# SCH2_Main_Computer.net
KiCad netlist of a schematic drawn in Altium Designer
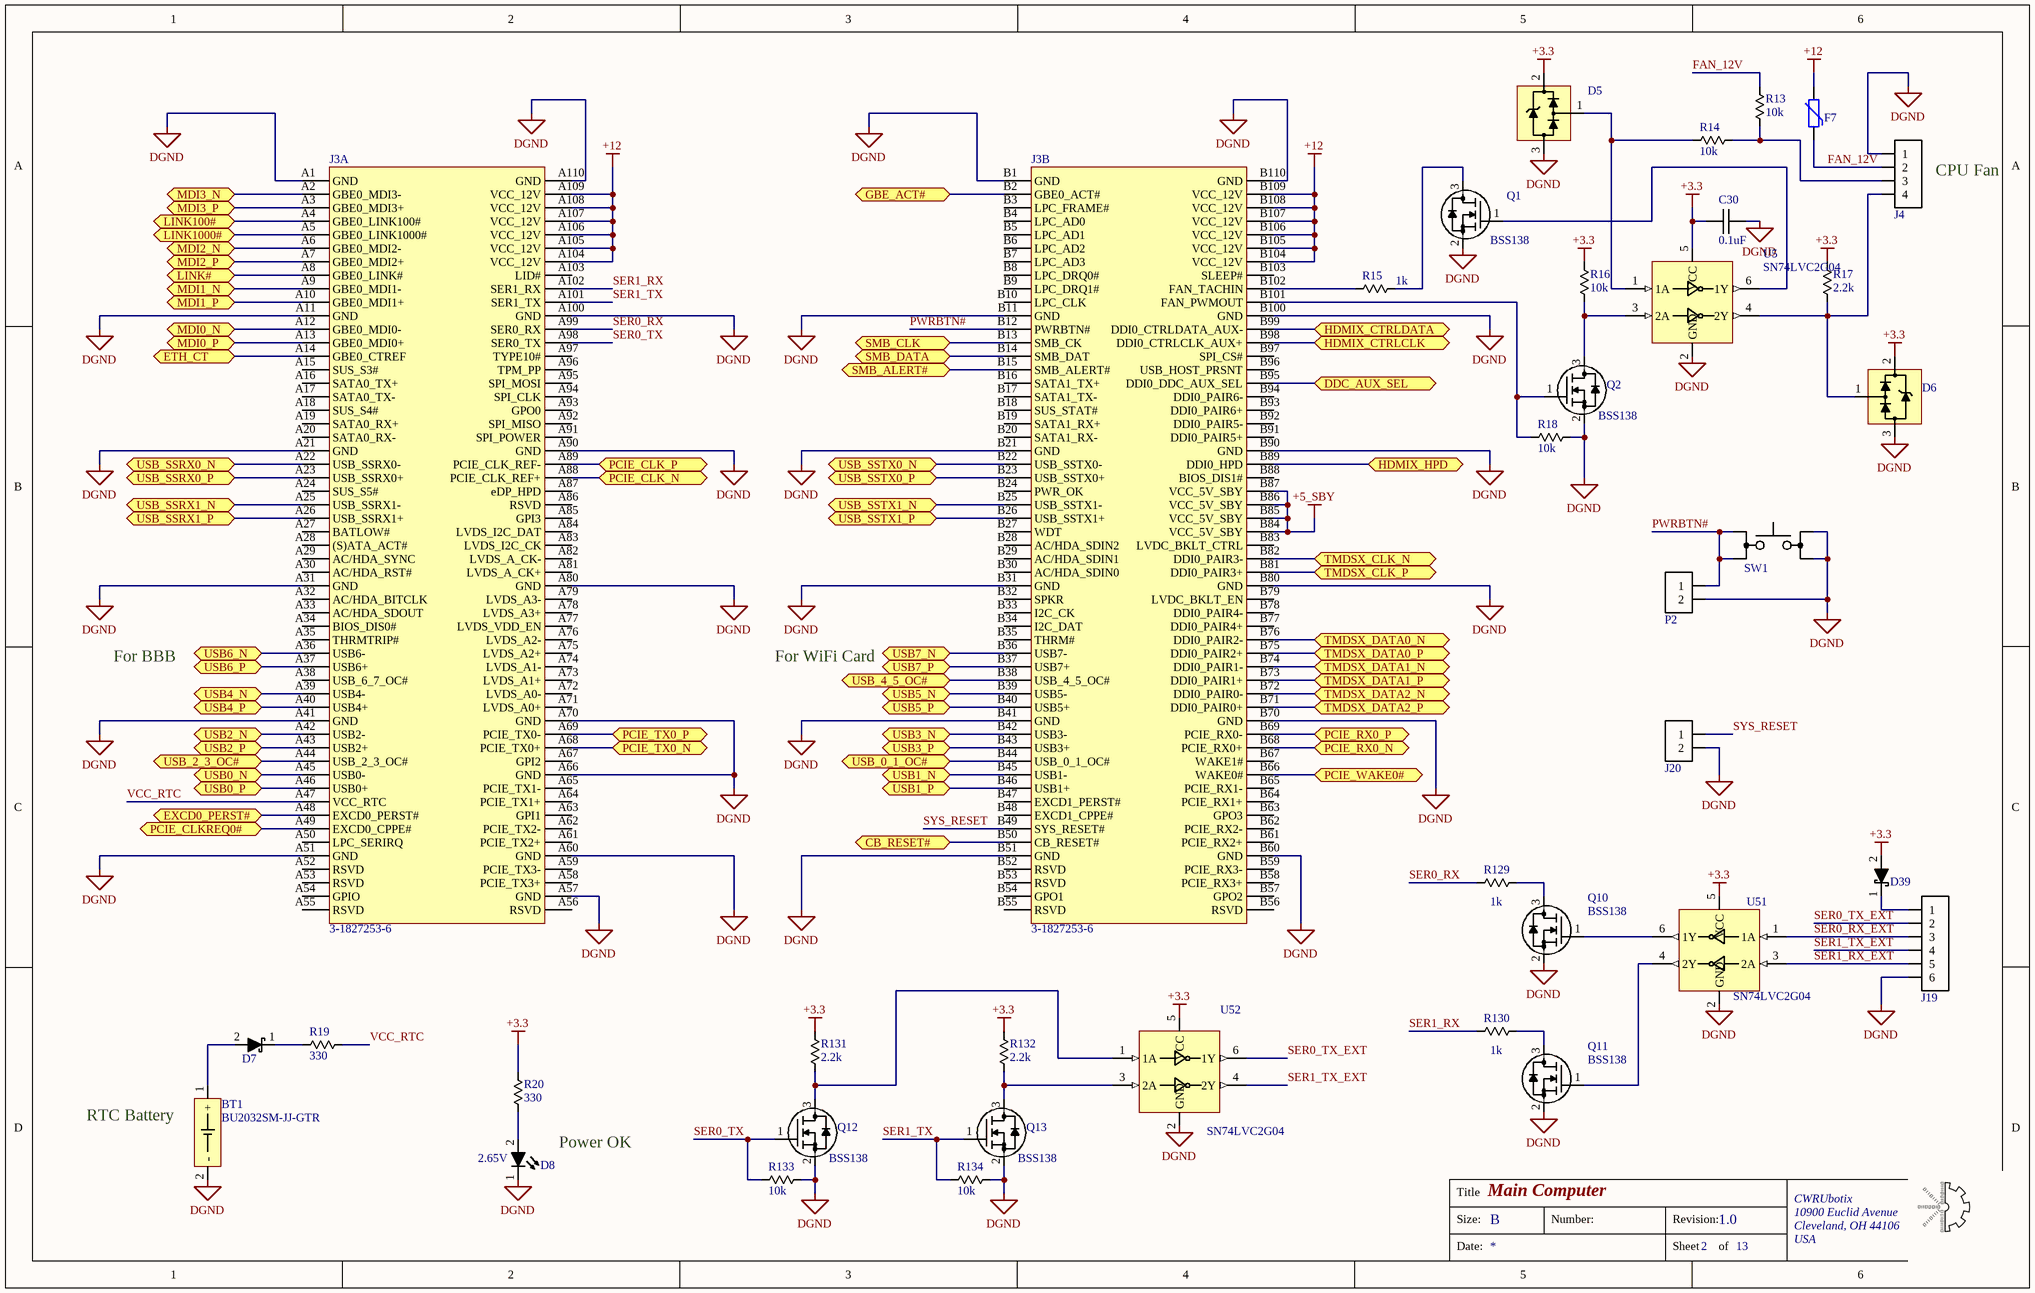
[diagram p0: SCH2_Main_Computer.SchDoc]

(export (version "E")
  (design (tool "Eeschema 10.0.6"))
  (components
    (comp (ref "BT1")
      (value "BU2032SM-JJ-GTR")
      (footprint "BU2032SM-JJ-GTR")
      (description "Battery Holder, Coin Cell CR2032, SMD")
      (fields
        (field (name "PART NUMBER") "CONN-00083")
        (field (name "MANUFACTURER") "Memory Protection Devices")
      )
      (libsource (lib "Connectors$") (part "CONN-00083"))
    )
    (comp (ref "C30")
      (value "0.1uF")
      (footprint "chip_0603")
      (description "CAP, 0.1uF, ±10%, 16V, X7R, 0603")
      (fields (field (name "PART NUMBER") "CAP-00542") (field (name "TOLERANCE") "±10%"))
      (libsource (lib "Capacitors$") (part "CAP-00542"))
    )
    (comp (ref "D5")
      (value "DLPT05")
      (footprint "sot-23-3")
      (description "TVS, Steering (Rail-Rail), 9.8V Clamping, 17A Peak Pulse, SOT-23")
      (fields (field (name "PART NUMBER") "DIO-00057") (field (name "MANUFACTURER") "Diodes Incorporated"))
      (libsource (lib "Diodes$") (part "DIO-00057"))
    )
    (comp (ref "D6")
      (value "DLPT05")
      (footprint "sot-23-3")
      (description "TVS, Steering (Rail-Rail), 9.8V Clamping, 17A Peak Pulse, SOT-23")
      (fields (field (name "PART NUMBER") "DIO-00057") (field (name "MANUFACTURER") "Diodes Incorporated"))
      (libsource (lib "") (part "DIO-00057_1"))
    )
    (comp (ref "D7")
      (value "diode_2")
      (footprint "sod123_0")
      (description "Dio Shtky, 1A, 0.55V, 40V, SOD-123")
      (fields (field (name "PART NUMBER") "DIO-00001") (field (name "MANUFACTURER") "ON Semi"))
      (libsource (lib "Diodes$") (part "DIO-00001"))
    )
    (comp (ref "D8")
      (value "diode_4")
      (footprint "chip_0603_LED")
      (description "LED, Blue, 0603, Low current, HELI2 Series")
      (fields
        (field (name "PART NUMBER") "DIO-00049")
        (field (name "FORWARD VOLTAGE") "2.65V")
        (field (name "MANUFACTURER") "Kingbright")
      )
      (libsource (lib "Diodes$") (part "DIO-00049"))
    )
    (comp (ref "D39")
      (value "diode_2")
      (footprint "sod123_0")
      (description "Dio Shtky, 1A, 0.55V, 40V, SOD-123")
      (fields (field (name "PART NUMBER") "DIO-00001") (field (name "MANUFACTURER") "ON Semi"))
      (libsource (lib "Diodes$") (part "DIO-00001"))
    )
    (comp (ref "F7")
      (value "PTC_0")
      (footprint "chip_1210")
      (description "PTC Fuse (Polyfuse), 16V 1.5A Hold, 3A Trip, 300ms")
      (fields (field (name "PART NUMBER") "MISC-00056") (field (name "MANUFACTURER") "Littelfuse"))
      (libsource (lib "Misc$") (part "MISC-00056"))
    )
    (comp (ref "J3")
      (value "3-1827253-6")
      (footprint "TE_CONN_1827253")
      (description "Plug, 220 pos, COM Express Board-Board connector")
      (fields (field (name "PART NUMBER") "CONN-00078") (field (name "MANUFACTURER") "TE Connectivity"))
      (libsource (lib "Connectors$") (part "CONN-00078"))
    )
    (comp (ref "J4")
      (value "conn-4x1_0")
      (footprint "MOLEX_0470531000")
      (description "Header, 4-Pos, Molex-47053, (CPU Fan Header)")
      (fields (field (name "PART NUMBER") "CONN-00087") (field (name "MANUFACTURER") "Molex"))
      (libsource (lib "Connectors$") (part "CONN-00087"))
    )
    (comp (ref "J19")
      (value "conn-6x1_0")
      (footprint "HDDR_6X1_0")
      (description "Header 6x1, 0.1\"")
      (fields (field (name "PART NUMBER") "CONN-00008"))
      (libsource (lib "Connectors$") (part "CONN-00008"))
    )
    (comp (ref "J20")
      (value "conn-2x1_0")
      (footprint "HDDR_2x1_0")
      (description "Header, 2x1, 0.1\"")
      (fields (field (name "PART NUMBER") "CONN-00055") (field (name "MANUFACTURER") "Samtec"))
      (libsource (lib "Connectors$") (part "CONN-00055"))
    )
    (comp (ref "P2")
      (value "conn-2x1_0")
      (footprint "HDDR_2x1_0")
      (description "Header, 2x1, 0.1\"")
      (fields (field (name "PART NUMBER") "CONN-00055") (field (name "MANUFACTURER") "Samtec"))
      (libsource (lib "Connectors$") (part "CONN-00055"))
    )
    (comp (ref "Q1")
      (value "n-mosfet_1")
      (footprint "sot-23-3")
      (description "XSTR NMOS, 220mA, 50V, Vgs 1.3V, SOT-23-3")
      (fields
        (field (name "PART NUMBER") "XSTR-00017")
        (field (name "MANUFACTURER") "ON Semi")
        (field (name "MANUFACTURER PN") "BSS138")
      )
      (libsource (lib "Transistors$") (part "XSTR-00017"))
    )
    (comp (ref "Q2")
      (value "n-mosfet_1")
      (footprint "sot-23-3")
      (description "XSTR NMOS, 220mA, 50V, Vgs 1.3V, SOT-23-3")
      (fields
        (field (name "PART NUMBER") "XSTR-00017")
        (field (name "MANUFACTURER") "ON Semi")
        (field (name "MANUFACTURER PN") "BSS138")
      )
      (libsource (lib "Transistors$") (part "XSTR-00017"))
    )
    (comp (ref "Q10")
      (value "n-mosfet_1")
      (footprint "sot-23-3")
      (description "XSTR NMOS, 220mA, 50V, Vgs 1.3V, SOT-23-3")
      (fields
        (field (name "PART NUMBER") "XSTR-00017")
        (field (name "MANUFACTURER") "ON Semi")
        (field (name "MANUFACTURER PN") "BSS138")
      )
      (libsource (lib "Transistors$") (part "XSTR-00017"))
    )
    (comp (ref "Q11")
      (value "n-mosfet_1")
      (footprint "sot-23-3")
      (description "XSTR NMOS, 220mA, 50V, Vgs 1.3V, SOT-23-3")
      (fields
        (field (name "PART NUMBER") "XSTR-00017")
        (field (name "MANUFACTURER") "ON Semi")
        (field (name "MANUFACTURER PN") "BSS138")
      )
      (libsource (lib "Transistors$") (part "XSTR-00017"))
    )
    (comp (ref "Q12")
      (value "n-mosfet_1")
      (footprint "sot-23-3")
      (description "XSTR NMOS, 220mA, 50V, Vgs 1.3V, SOT-23-3")
      (fields
        (field (name "PART NUMBER") "XSTR-00017")
        (field (name "MANUFACTURER") "ON Semi")
        (field (name "MANUFACTURER PN") "BSS138")
      )
      (libsource (lib "Transistors$") (part "XSTR-00017"))
    )
    (comp (ref "Q13")
      (value "n-mosfet_1")
      (footprint "sot-23-3")
      (description "XSTR NMOS, 220mA, 50V, Vgs 1.3V, SOT-23-3")
      (fields
        (field (name "PART NUMBER") "XSTR-00017")
        (field (name "MANUFACTURER") "ON Semi")
        (field (name "MANUFACTURER PN") "BSS138")
      )
      (libsource (lib "Transistors$") (part "XSTR-00017"))
    )
    (comp (ref "R13")
      (value "10k")
      (footprint "chip_0603")
      (description "RES SMD 10K OHM 1% 1/4W 0603")
      (fields (field (name "PART NUMBER") "RES-00306") (field (name "TOLERANCE") "1%"))
      (libsource (lib "Resistors$") (part "RES-00306"))
    )
    (comp (ref "R14")
      (value "10k")
      (footprint "chip_0603")
      (description "RES SMD 10K OHM 1% 1/4W 0603")
      (fields (field (name "PART NUMBER") "RES-00306") (field (name "TOLERANCE") "1%"))
      (libsource (lib "Resistors$") (part "RES-00306"))
    )
    (comp (ref "R15")
      (value "1k")
      (footprint "chip_0603")
      (description "RES SMD 1K OHM 1% 1/4W 0603")
      (fields (field (name "PART NUMBER") "RES-00360") (field (name "TOLERANCE") "1%"))
      (libsource (lib "Resistors$") (part "RES-00360"))
    )
    (comp (ref "R16")
      (value "10k")
      (footprint "chip_0603")
      (description "RES SMD 10K OHM 1% 1/4W 0603")
      (fields (field (name "PART NUMBER") "RES-00306") (field (name "TOLERANCE") "1%"))
      (libsource (lib "Resistors$") (part "RES-00306"))
    )
    (comp (ref "R17")
      (value "2.2k")
      (footprint "chip_0603")
      (description "RES SMD 2.2K OHM 1% 1/4W 0603")
      (fields (field (name "PART NUMBER") "RES-00365") (field (name "TOLERANCE") "1%"))
      (libsource (lib "Resistors$") (part "RES-00365"))
    )
    (comp (ref "R18")
      (value "10k")
      (footprint "chip_0603")
      (description "RES SMD 10K OHM 1% 1/4W 0603")
      (fields (field (name "PART NUMBER") "RES-00306") (field (name "TOLERANCE") "1%"))
      (libsource (lib "Resistors$") (part "RES-00306"))
    )
    (comp (ref "R19")
      (value "330")
      (footprint "chip_0603")
      (description "RES SMD 330 OHM 1% 1/4W 0603")
      (fields (field (name "PART NUMBER") "RES-00221") (field (name "TOLERANCE") "1%"))
      (libsource (lib "Resistors$") (part "RES-00221"))
    )
    (comp (ref "R20")
      (value "330")
      (footprint "chip_0603")
      (description "RES SMD 330 OHM 1% 1/4W 0603")
      (fields (field (name "PART NUMBER") "RES-00221") (field (name "TOLERANCE") "1%"))
      (libsource (lib "Resistors$") (part "RES-00221"))
    )
    (comp (ref "R129")
      (value "1k")
      (footprint "chip_0603")
      (description "RES SMD 1K OHM 1% 1/4W 0603")
      (fields (field (name "PART NUMBER") "RES-00360") (field (name "TOLERANCE") "1%"))
      (libsource (lib "Resistors$") (part "RES-00360"))
    )
    (comp (ref "R130")
      (value "1k")
      (footprint "chip_0603")
      (description "RES SMD 1K OHM 1% 1/4W 0603")
      (fields (field (name "PART NUMBER") "RES-00360") (field (name "TOLERANCE") "1%"))
      (libsource (lib "Resistors$") (part "RES-00360"))
    )
    (comp (ref "R131")
      (value "2.2k")
      (footprint "chip_0603")
      (description "RES SMD 2.2K OHM 1% 1/4W 0603")
      (fields (field (name "PART NUMBER") "RES-00365") (field (name "TOLERANCE") "1%"))
      (libsource (lib "Resistors$") (part "RES-00365"))
    )
    (comp (ref "R132")
      (value "2.2k")
      (footprint "chip_0603")
      (description "RES SMD 2.2K OHM 1% 1/4W 0603")
      (fields (field (name "PART NUMBER") "RES-00365") (field (name "TOLERANCE") "1%"))
      (libsource (lib "Resistors$") (part "RES-00365"))
    )
    (comp (ref "R133")
      (value "10k")
      (footprint "chip_0603")
      (description "RES SMD 10K OHM 1% 1/4W 0603")
      (fields (field (name "PART NUMBER") "RES-00306") (field (name "TOLERANCE") "1%"))
      (libsource (lib "Resistors$") (part "RES-00306"))
    )
    (comp (ref "R134")
      (value "10k")
      (footprint "chip_0603")
      (description "RES SMD 10K OHM 1% 1/4W 0603")
      (fields (field (name "PART NUMBER") "RES-00306") (field (name "TOLERANCE") "1%"))
      (libsource (lib "Resistors$") (part "RES-00306"))
    )
    (comp (ref "SW1")
      (value "SW_1P1T_2")
      (footprint "B3FS-1000")
      (description "Switch, SPST-NO, Tactile, 6.3x6.0mm, SMD, 50mA 24VDC")
      (fields (field (name "PART NUMBER") "MISC-00042") (field (name "MANUFACTURER") "Omron"))
      (libsource (lib "Misc$") (part "MISC-00042"))
    )
    (comp (ref "U5")
      (value "SN74LVC2G04")
      (footprint "sot-23-6")
      (description "Inverter, Dual, sot-23-6, SN74LVC2G04")
      (fields (field (name "PART NUMBER") "LOGIC-00001") (field (name "MANUFACTURER") "TI"))
      (libsource (lib "") (part "LOGIC-00001_1"))
    )
    (comp (ref "U51")
      (value "SN74LVC2G04")
      (footprint "sot-23-6")
      (description "Inverter, Dual, sot-23-6, SN74LVC2G04")
      (fields (field (name "PART NUMBER") "LOGIC-00001") (field (name "MANUFACTURER") "TI"))
      (libsource (lib "Logic$") (part "LOGIC-00001"))
    )
    (comp (ref "U52")
      (value "SN74LVC2G04")
      (footprint "sot-23-6")
      (description "Inverter, Dual, sot-23-6, SN74LVC2G04")
      (fields (field (name "PART NUMBER") "LOGIC-00001") (field (name "MANUFACTURER") "TI"))
      (libsource (lib "") (part "LOGIC-00001_1"))
    )
  )
  (nets
    (net (code "1") (name "+3.3") (class "Default")
      (node (ref "C30") (pin "1") (pinfunction "1_1") (pintype "passive"))
      (node (ref "D39") (pin "2") (pinfunction "2_2") (pintype "passive"))
      (node (ref "D5") (pin "2") (pinfunction "VCC_2") (pintype "passive"))
      (node (ref "D6") (pin "2") (pinfunction "VCC_2") (pintype "passive"))
      (node (ref "R131") (pin "1") (pinfunction "1_1") (pintype "passive"))
      (node (ref "R132") (pin "1") (pinfunction "1_1") (pintype "passive"))
      (node (ref "R16") (pin "1") (pinfunction "1_1") (pintype "passive"))
      (node (ref "R17") (pin "1") (pinfunction "1_1") (pintype "passive"))
      (node (ref "R20") (pin "2") (pinfunction "2_2") (pintype "passive"))
      (node (ref "U5") (pin "5") (pinfunction "VCC_5") (pintype "power_in"))
      (node (ref "U51") (pin "5") (pinfunction "VCC_5") (pintype "power_in"))
      (node (ref "U52") (pin "5") (pinfunction "VCC_5") (pintype "power_in"))
    )
    (net (code "2") (name "+5_SBY") (class "Default")
      (node (ref "J3") (pin "B84") (pinfunction "VCC_5V_SBY_B84") (pintype "passive"))
      (node (ref "J3") (pin "B85") (pinfunction "VCC_5V_SBY_B85") (pintype "passive"))
      (node (ref "J3") (pin "B86") (pinfunction "VCC_5V_SBY_B86") (pintype "passive"))
      (node (ref "J3") (pin "B87") (pinfunction "VCC_5V_SBY_B87") (pintype "passive"))
    )
    (net (code "3") (name "+12") (class "Default")
      (node (ref "F7") (pin "2") (pinfunction "2_2") (pintype "passive"))
      (node (ref "J3") (pin "A104") (pinfunction "VCC_12V_A104") (pintype "passive"))
      (node (ref "J3") (pin "A105") (pinfunction "VCC_12V_A105") (pintype "passive"))
      (node (ref "J3") (pin "A106") (pinfunction "VCC_12V_A106") (pintype "passive"))
      (node (ref "J3") (pin "A107") (pinfunction "VCC_12V_A107") (pintype "passive"))
      (node (ref "J3") (pin "A108") (pinfunction "VCC_12V_A108") (pintype "passive"))
      (node (ref "J3") (pin "A109") (pinfunction "VCC_12V_A109") (pintype "passive"))
      (node (ref "J3") (pin "B104") (pinfunction "VCC_12V_B104") (pintype "passive"))
      (node (ref "J3") (pin "B105") (pinfunction "VCC_12V_B105") (pintype "passive"))
      (node (ref "J3") (pin "B106") (pinfunction "VCC_12V_B106") (pintype "passive"))
      (node (ref "J3") (pin "B107") (pinfunction "VCC_12V_B107") (pintype "passive"))
      (node (ref "J3") (pin "B108") (pinfunction "VCC_12V_B108") (pintype "passive"))
      (node (ref "J3") (pin "B109") (pinfunction "VCC_12V_B109") (pintype "passive"))
    )
    (net (code "4") (name "/CB_RESET#") (class "Default")
      (node (ref "J3") (pin "B50") (pinfunction "CB_RESET#_B50") (pintype "passive"))
    )
    (net (code "5") (name "/DDC_AUX_SEL") (class "Default")
      (node (ref "J3") (pin "B95") (pinfunction "DDI0_DDC_AUX_SEL_B95") (pintype "passive"))
    )
    (net (code "6") (name "/ETH_CT") (class "Default")
      (node (ref "J3") (pin "A14") (pinfunction "GBE0_CTREF_A14") (pintype "passive"))
    )
    (net (code "7") (name "/EXCD0_PERST#") (class "Default")
      (node (ref "J3") (pin "A48") (pinfunction "EXCD0_PERST#_A48") (pintype "passive"))
    )
    (net (code "8") (name "/FAN_12V") (class "Default")
      (node (ref "F7") (pin "1") (pinfunction "1_1") (pintype "passive"))
      (node (ref "J4") (pin "2") (pinfunction "2_2") (pintype "passive"))
      (node (ref "R13") (pin "2") (pinfunction "2_2") (pintype "passive"))
    )
    (net (code "9") (name "/GBE_ACT#") (class "Default")
      (node (ref "J3") (pin "B2") (pinfunction "GBE0_ACT#_B2") (pintype "passive"))
    )
    (net (code "10") (name "/HDMIX_CTRLCLK") (class "Default")
      (node (ref "J3") (pin "B98") (pinfunction "DDI0_CTRLCLK_AUX+_B98") (pintype "passive"))
    )
    (net (code "11") (name "/HDMIX_CTRLDATA") (class "Default")
      (node (ref "J3") (pin "B99") (pinfunction "DDI0_CTRLDATA_AUX-_B99") (pintype "passive"))
    )
    (net (code "12") (name "/HDMIX_HPD") (class "Default")
      (node (ref "J3") (pin "B89") (pinfunction "DDI0_HPD_B89") (pintype "passive"))
    )
    (net (code "13") (name "/LINK#") (class "Default")
      (node (ref "J3") (pin "A8") (pinfunction "GBE0_LINK#_A8") (pintype "passive"))
    )
    (net (code "14") (name "/LINK100#") (class "Default")
      (node (ref "J3") (pin "A4") (pinfunction "GBE0_LINK100#_A4") (pintype "passive"))
    )
    (net (code "15") (name "/LINK1000#") (class "Default")
      (node (ref "J3") (pin "A5") (pinfunction "GBE0_LINK1000#_A5") (pintype "passive"))
    )
    (net (code "16") (name "/MDI0_N") (class "Default")
      (node (ref "J3") (pin "A12") (pinfunction "GBE0_MDI0-_A12") (pintype "passive"))
    )
    (net (code "17") (name "/MDI0_P") (class "Default")
      (node (ref "J3") (pin "A13") (pinfunction "GBE0_MDI0+_A13") (pintype "passive"))
    )
    (net (code "18") (name "/MDI1_N") (class "Default")
      (node (ref "J3") (pin "A9") (pinfunction "GBE0_MDI1-_A9") (pintype "passive"))
    )
    (net (code "19") (name "/MDI1_P") (class "Default")
      (node (ref "J3") (pin "A10") (pinfunction "GBE0_MDI1+_A10") (pintype "passive"))
    )
    (net (code "20") (name "/MDI2_N") (class "Default")
      (node (ref "J3") (pin "A6") (pinfunction "GBE0_MDI2-_A6") (pintype "passive"))
    )
    (net (code "21") (name "/MDI2_P") (class "Default")
      (node (ref "J3") (pin "A7") (pinfunction "GBE0_MDI2+_A7") (pintype "passive"))
    )
    (net (code "22") (name "/MDI3_N") (class "Default")
      (node (ref "J3") (pin "A2") (pinfunction "GBE0_MDI3-_A2") (pintype "passive"))
    )
    (net (code "23") (name "/MDI3_P") (class "Default")
      (node (ref "J3") (pin "A3") (pinfunction "GBE0_MDI3+_A3") (pintype "passive"))
    )
    (net (code "24") (name "/PCIE_CLKREQ0#") (class "Default")
      (node (ref "J3") (pin "A49") (pinfunction "EXCD0_CPPE#_A49") (pintype "passive"))
    )
    (net (code "25") (name "/PCIE_CLK_N") (class "Default")
      (node (ref "J3") (pin "A88") (pinfunction "PCIE_CLK_REF+_A88") (pintype "passive"))
    )
    (net (code "26") (name "/PCIE_CLK_P") (class "Default")
      (node (ref "J3") (pin "A89") (pinfunction "PCIE_CLK_REF-_A89") (pintype "passive"))
    )
    (net (code "27") (name "/PCIE_RX0_N") (class "Default")
      (node (ref "J3") (pin "B68") (pinfunction "PCIE_RX0+_B68") (pintype "passive"))
    )
    (net (code "28") (name "/PCIE_RX0_P") (class "Default")
      (node (ref "J3") (pin "B69") (pinfunction "PCIE_RX0-_B69") (pintype "passive"))
    )
    (net (code "29") (name "/PCIE_TX0_N") (class "Default")
      (node (ref "J3") (pin "A68") (pinfunction "PCIE_TX0+_A68") (pintype "passive"))
    )
    (net (code "30") (name "/PCIE_TX0_P") (class "Default")
      (node (ref "J3") (pin "A69") (pinfunction "PCIE_TX0-_A69") (pintype "passive"))
    )
    (net (code "31") (name "/PCIE_WAKE0#") (class "Default")
      (node (ref "J3") (pin "B66") (pinfunction "WAKE0#_B66") (pintype "passive"))
    )
    (net (code "32") (name "/PWRBTN#") (class "Default")
      (node (ref "J3") (pin "B12") (pinfunction "PWRBTN#_B12") (pintype "passive"))
      (node (ref "P2") (pin "1") (pinfunction "1_1") (pintype "passive"))
      (node (ref "SW1") (pin "1") (pinfunction "1_1") (pintype "passive"))
      (node (ref "SW1") (pin "2") (pinfunction "2_2") (pintype "passive"))
    )
    (net (code "33") (name "/SER0_RX") (class "Default")
      (node (ref "J3") (pin "A99") (pinfunction "SER0_RX_A99") (pintype "passive"))
      (node (ref "R129") (pin "1") (pinfunction "1_1") (pintype "passive"))
    )
    (net (code "34") (name "/SER0_RX_EXT") (class "Default")
      (node (ref "J19") (pin "3") (pinfunction "3_3") (pintype "passive"))
      (node (ref "U51") (pin "1") (pinfunction "1A_1") (pintype "input"))
    )
    (net (code "35") (name "/SER0_TX") (class "Default")
      (node (ref "J3") (pin "A98") (pinfunction "SER0_TX_A98") (pintype "passive"))
      (node (ref "Q12") (pin "1") (pinfunction "G_1") (pintype "passive"))
      (node (ref "R133") (pin "1") (pinfunction "1_1") (pintype "passive"))
    )
    (net (code "36") (name "/SER0_TX_EXT") (class "Default")
      (node (ref "J19") (pin "2") (pinfunction "2_2") (pintype "passive"))
      (node (ref "U52") (pin "6") (pinfunction "1Y_6") (pintype "output"))
    )
    (net (code "37") (name "/SER1_RX") (class "Default")
      (node (ref "J3") (pin "A102") (pinfunction "SER1_RX_A102") (pintype "passive"))
      (node (ref "R130") (pin "1") (pinfunction "1_1") (pintype "passive"))
    )
    (net (code "38") (name "/SER1_RX_EXT") (class "Default")
      (node (ref "J19") (pin "5") (pinfunction "5_5") (pintype "passive"))
      (node (ref "U51") (pin "3") (pinfunction "2A_3") (pintype "input"))
    )
    (net (code "39") (name "/SER1_TX") (class "Default")
      (node (ref "J3") (pin "A101") (pinfunction "SER1_TX_A101") (pintype "passive"))
      (node (ref "Q13") (pin "1") (pinfunction "G_1") (pintype "passive"))
      (node (ref "R134") (pin "1") (pinfunction "1_1") (pintype "passive"))
    )
    (net (code "40") (name "/SER1_TX_EXT") (class "Default")
      (node (ref "J19") (pin "4") (pinfunction "4_4") (pintype "passive"))
      (node (ref "U52") (pin "4") (pinfunction "2Y_4") (pintype "output"))
    )
    (net (code "41") (name "/SMB_ALERT#") (class "Default")
      (node (ref "J3") (pin "B15") (pinfunction "SMB_ALERT#_B15") (pintype "passive"))
    )
    (net (code "42") (name "/SMB_CLK") (class "Default")
      (node (ref "J3") (pin "B13") (pinfunction "SMB_CK_B13") (pintype "passive"))
    )
    (net (code "43") (name "/SMB_DATA") (class "Default")
      (node (ref "J3") (pin "B14") (pinfunction "SMB_DAT_B14") (pintype "passive"))
    )
    (net (code "44") (name "/SYS_RESET") (class "Default")
      (node (ref "J20") (pin "1") (pinfunction "1_1") (pintype "passive"))
      (node (ref "J3") (pin "B49") (pinfunction "SYS_RESET#_B49") (pintype "passive"))
    )
    (net (code "45") (name "/TMDSX_CLK_N") (class "Default")
      (node (ref "J3") (pin "B82") (pinfunction "DDI0_PAIR3-_B82") (pintype "passive"))
    )
    (net (code "46") (name "/TMDSX_CLK_P") (class "Default")
      (node (ref "J3") (pin "B81") (pinfunction "DDI0_PAIR3+_B81") (pintype "passive"))
    )
    (net (code "47") (name "/TMDSX_DATA0_N") (class "Default")
      (node (ref "J3") (pin "B76") (pinfunction "DDI0_PAIR2-_B76") (pintype "passive"))
    )
    (net (code "48") (name "/TMDSX_DATA0_P") (class "Default")
      (node (ref "J3") (pin "B75") (pinfunction "DDI0_PAIR2+_B75") (pintype "passive"))
    )
    (net (code "49") (name "/TMDSX_DATA1_N") (class "Default")
      (node (ref "J3") (pin "B74") (pinfunction "DDI0_PAIR1-_B74") (pintype "passive"))
    )
    (net (code "50") (name "/TMDSX_DATA1_P") (class "Default")
      (node (ref "J3") (pin "B73") (pinfunction "DDI0_PAIR1+_B73") (pintype "passive"))
    )
    (net (code "51") (name "/TMDSX_DATA2_N") (class "Default")
      (node (ref "J3") (pin "B72") (pinfunction "DDI0_PAIR0-_B72") (pintype "passive"))
    )
    (net (code "52") (name "/TMDSX_DATA2_P") (class "Default")
      (node (ref "J3") (pin "B71") (pinfunction "DDI0_PAIR0+_B71") (pintype "passive"))
    )
    (net (code "53") (name "/USB0_N") (class "Default")
      (node (ref "J3") (pin "A45") (pinfunction "USB0-_A45") (pintype "passive"))
    )
    (net (code "54") (name "/USB0_P") (class "Default")
      (node (ref "J3") (pin "A46") (pinfunction "USB0+_A46") (pintype "passive"))
    )
    (net (code "55") (name "/USB1_N") (class "Default")
      (node (ref "J3") (pin "B45") (pinfunction "USB1-_B45") (pintype "passive"))
    )
    (net (code "56") (name "/USB1_P") (class "Default")
      (node (ref "J3") (pin "B46") (pinfunction "USB1+_B46") (pintype "passive"))
    )
    (net (code "57") (name "/USB2_N") (class "Default")
      (node (ref "J3") (pin "A42") (pinfunction "USB2-_A42") (pintype "passive"))
    )
    (net (code "58") (name "/USB2_P") (class "Default")
      (node (ref "J3") (pin "A43") (pinfunction "USB2+_A43") (pintype "passive"))
    )
    (net (code "59") (name "/USB3_N") (class "Default")
      (node (ref "J3") (pin "B42") (pinfunction "USB3-_B42") (pintype "passive"))
    )
    (net (code "60") (name "/USB3_P") (class "Default")
      (node (ref "J3") (pin "B43") (pinfunction "USB3+_B43") (pintype "passive"))
    )
    (net (code "61") (name "/USB4_N") (class "Default")
      (node (ref "J3") (pin "A39") (pinfunction "USB4-_A39") (pintype "passive"))
    )
    (net (code "62") (name "/USB4_P") (class "Default")
      (node (ref "J3") (pin "A40") (pinfunction "USB4+_A40") (pintype "passive"))
    )
    (net (code "63") (name "/USB5_N") (class "Default")
      (node (ref "J3") (pin "B39") (pinfunction "USB5-_B39") (pintype "passive"))
    )
    (net (code "64") (name "/USB5_P") (class "Default")
      (node (ref "J3") (pin "B40") (pinfunction "USB5+_B40") (pintype "passive"))
    )
    (net (code "65") (name "/USB6_N") (class "Default")
      (node (ref "J3") (pin "A36") (pinfunction "USB6-_A36") (pintype "passive"))
    )
    (net (code "66") (name "/USB6_P") (class "Default")
      (node (ref "J3") (pin "A37") (pinfunction "USB6+_A37") (pintype "passive"))
    )
    (net (code "67") (name "/USB7_N") (class "Default")
      (node (ref "J3") (pin "B36") (pinfunction "USB7-_B36") (pintype "passive"))
    )
    (net (code "68") (name "/USB7_P") (class "Default")
      (node (ref "J3") (pin "B37") (pinfunction "USB7+_B37") (pintype "passive"))
    )
    (net (code "69") (name "/USB_0_1_OC#") (class "Default")
      (node (ref "J3") (pin "B44") (pinfunction "USB_0_1_OC#_B44") (pintype "passive"))
    )
    (net (code "70") (name "/USB_2_3_OC#") (class "Default")
      (node (ref "J3") (pin "A44") (pinfunction "USB_2_3_OC#_A44") (pintype "passive"))
    )
    (net (code "71") (name "/USB_4_5_OC#") (class "Default")
      (node (ref "J3") (pin "B38") (pinfunction "USB_4_5_OC#_B38") (pintype "passive"))
    )
    (net (code "72") (name "/USB_SSRX0_N") (class "Default")
      (node (ref "J3") (pin "A22") (pinfunction "USB_SSRX0-_A22") (pintype "passive"))
    )
    (net (code "73") (name "/USB_SSRX0_P") (class "Default")
      (node (ref "J3") (pin "A23") (pinfunction "USB_SSRX0+_A23") (pintype "passive"))
    )
    (net (code "74") (name "/USB_SSRX1_N") (class "Default")
      (node (ref "J3") (pin "A25") (pinfunction "USB_SSRX1-_A25") (pintype "passive"))
    )
    (net (code "75") (name "/USB_SSRX1_P") (class "Default")
      (node (ref "J3") (pin "A26") (pinfunction "USB_SSRX1+_A26") (pintype "passive"))
    )
    (net (code "76") (name "/USB_SSTX0_N") (class "Default")
      (node (ref "J3") (pin "B22") (pinfunction "USB_SSTX0-_B22") (pintype "passive"))
    )
    (net (code "77") (name "/USB_SSTX0_P") (class "Default")
      (node (ref "J3") (pin "B23") (pinfunction "USB_SSTX0+_B23") (pintype "passive"))
    )
    (net (code "78") (name "/USB_SSTX1_N") (class "Default")
      (node (ref "J3") (pin "B25") (pinfunction "USB_SSTX1-_B25") (pintype "passive"))
    )
    (net (code "79") (name "/USB_SSTX1_P") (class "Default")
      (node (ref "J3") (pin "B26") (pinfunction "USB_SSTX1+_B26") (pintype "passive"))
    )
    (net (code "80") (name "/VCC_RTC") (class "Default")
      (node (ref "J3") (pin "A47") (pinfunction "VCC_RTC_A47") (pintype "passive"))
      (node (ref "R19") (pin "2") (pinfunction "2_2") (pintype "passive"))
    )
    (net (code "81") (name "DGND") (class "Default")
      (node (ref "BT1") (pin "2") (pinfunction "-_2") (pintype "passive"))
      (node (ref "C30") (pin "2") (pinfunction "2_2") (pintype "passive"))
      (node (ref "D5") (pin "3") (pinfunction "GND_3") (pintype "passive"))
      (node (ref "D6") (pin "3") (pinfunction "GND_3") (pintype "passive"))
      (node (ref "D8") (pin "1") (pinfunction "1_1") (pintype "passive"))
      (node (ref "J19") (pin "6") (pinfunction "6_6") (pintype "passive"))
      (node (ref "J20") (pin "2") (pinfunction "2_2") (pintype "passive"))
      (node (ref "J3") (pin "A1") (pinfunction "GND_A1") (pintype "passive"))
      (node (ref "J3") (pin "A100") (pinfunction "GND_A100") (pintype "passive"))
      (node (ref "J3") (pin "A11") (pinfunction "GND_A11") (pintype "passive"))
      (node (ref "J3") (pin "A110") (pinfunction "GND_A110") (pintype "passive"))
      (node (ref "J3") (pin "A21") (pinfunction "GND_A21") (pintype "passive"))
      (node (ref "J3") (pin "A31") (pinfunction "GND_A31") (pintype "passive"))
      (node (ref "J3") (pin "A41") (pinfunction "GND_A41") (pintype "passive"))
      (node (ref "J3") (pin "A51") (pinfunction "GND_A51") (pintype "passive"))
      (node (ref "J3") (pin "A57") (pinfunction "GND_A57") (pintype "passive"))
      (node (ref "J3") (pin "A60") (pinfunction "GND_A60") (pintype "passive"))
      (node (ref "J3") (pin "A66") (pinfunction "GND_A66") (pintype "passive"))
      (node (ref "J3") (pin "A70") (pinfunction "GND_A70") (pintype "passive"))
      (node (ref "J3") (pin "A80") (pinfunction "GND_A80") (pintype "passive"))
      (node (ref "J3") (pin "A90") (pinfunction "GND_A90") (pintype "passive"))
      (node (ref "J3") (pin "B1") (pinfunction "GND_B1") (pintype "passive"))
      (node (ref "J3") (pin "B100") (pinfunction "GND_B100") (pintype "passive"))
      (node (ref "J3") (pin "B11") (pinfunction "GND_B11") (pintype "passive"))
      (node (ref "J3") (pin "B110") (pinfunction "GND_B110") (pintype "passive"))
      (node (ref "J3") (pin "B21") (pinfunction "GND_B21") (pintype "passive"))
      (node (ref "J3") (pin "B31") (pinfunction "GND_B31") (pintype "passive"))
      (node (ref "J3") (pin "B41") (pinfunction "GND_B41") (pintype "passive"))
      (node (ref "J3") (pin "B51") (pinfunction "GND_B51") (pintype "passive"))
      (node (ref "J3") (pin "B60") (pinfunction "GND_B60") (pintype "passive"))
      (node (ref "J3") (pin "B70") (pinfunction "GND_B70") (pintype "passive"))
      (node (ref "J3") (pin "B80") (pinfunction "GND_B80") (pintype "passive"))
      (node (ref "J3") (pin "B90") (pinfunction "GND_B90") (pintype "passive"))
      (node (ref "J4") (pin "1") (pinfunction "1_1") (pintype "passive"))
      (node (ref "P2") (pin "2") (pinfunction "2_2") (pintype "passive"))
      (node (ref "Q1") (pin "2") (pinfunction "S_2") (pintype "passive"))
      (node (ref "Q10") (pin "2") (pinfunction "S_2") (pintype "passive"))
      (node (ref "Q11") (pin "2") (pinfunction "S_2") (pintype "passive"))
      (node (ref "Q12") (pin "2") (pinfunction "S_2") (pintype "passive"))
      (node (ref "Q13") (pin "2") (pinfunction "S_2") (pintype "passive"))
      (node (ref "Q2") (pin "2") (pinfunction "S_2") (pintype "passive"))
      (node (ref "R133") (pin "2") (pinfunction "2_2") (pintype "passive"))
      (node (ref "R134") (pin "2") (pinfunction "2_2") (pintype "passive"))
      (node (ref "R18") (pin "2") (pinfunction "2_2") (pintype "passive"))
      (node (ref "SW1") (pin "3") (pinfunction "3_3") (pintype "passive"))
      (node (ref "SW1") (pin "4") (pinfunction "4_4") (pintype "passive"))
      (node (ref "U5") (pin "2") (pinfunction "GND_2") (pintype "power_in"))
      (node (ref "U51") (pin "2") (pinfunction "GND_2") (pintype "power_in"))
      (node (ref "U52") (pin "2") (pinfunction "GND_2") (pintype "power_in"))
    )
    (net (code "82") (name "Net-(BT1-+)") (class "Default")
      (node (ref "BT1") (pin "1") (pinfunction "+_1") (pintype "passive"))
      (node (ref "D7") (pin "2") (pinfunction "2_2") (pintype "passive"))
    )
    (net (code "83") (name "Net-(D5-LINE)") (class "Default")
      (node (ref "D5") (pin "1") (pinfunction "LINE_1") (pintype "passive"))
      (node (ref "R14") (pin "1") (pinfunction "1_1") (pintype "passive"))
      (node (ref "U5") (pin "1") (pinfunction "1A_1") (pintype "input"))
    )
    (net (code "84") (name "Net-(D6-LINE)") (class "Default")
      (node (ref "D6") (pin "1") (pinfunction "LINE_1") (pintype "passive"))
      (node (ref "J4") (pin "4") (pinfunction "4_4") (pintype "passive"))
      (node (ref "R17") (pin "2") (pinfunction "2_2") (pintype "passive"))
      (node (ref "U5") (pin "4") (pinfunction "2Y_4") (pintype "output"))
    )
    (net (code "85") (name "Net-(D7-Pad1)") (class "Default")
      (node (ref "D7") (pin "1") (pinfunction "1_1") (pintype "passive"))
      (node (ref "R19") (pin "1") (pinfunction "1_1") (pintype "passive"))
    )
    (net (code "86") (name "Net-(D8-Pad2)") (class "Default")
      (node (ref "D8") (pin "2") (pinfunction "2_2") (pintype "passive"))
      (node (ref "R20") (pin "1") (pinfunction "1_1") (pintype "passive"))
    )
    (net (code "87") (name "Net-(D39-Pad1)") (class "Default")
      (node (ref "D39") (pin "1") (pinfunction "1_1") (pintype "passive"))
      (node (ref "J19") (pin "1") (pinfunction "1_1") (pintype "passive"))
    )
    (net (code "88") (name "Net-(J3B-FAN_PWMOUT)") (class "Default")
      (node (ref "J3") (pin "B101") (pinfunction "FAN_PWMOUT_B101") (pintype "passive"))
      (node (ref "Q2") (pin "1") (pinfunction "G_1") (pintype "passive"))
      (node (ref "R18") (pin "1") (pinfunction "1_1") (pintype "passive"))
    )
    (net (code "89") (name "Net-(J3B-FAN_TACHIN)") (class "Default")
      (node (ref "J3") (pin "B102") (pinfunction "FAN_TACHIN_B102") (pintype "passive"))
      (node (ref "R15") (pin "1") (pinfunction "1_1") (pintype "passive"))
    )
    (net (code "90") (name "Net-(J4-Pad3)") (class "Default")
      (node (ref "J4") (pin "3") (pinfunction "3_3") (pintype "passive"))
      (node (ref "R13") (pin "1") (pinfunction "1_1") (pintype "passive"))
      (node (ref "R14") (pin "2") (pinfunction "2_2") (pintype "passive"))
    )
    (net (code "91") (name "Net-(Q1-D)") (class "Default")
      (node (ref "Q1") (pin "3") (pinfunction "D_3") (pintype "passive"))
      (node (ref "R15") (pin "2") (pinfunction "2_2") (pintype "passive"))
    )
    (net (code "92") (name "Net-(Q1-G)") (class "Default")
      (node (ref "Q1") (pin "1") (pinfunction "G_1") (pintype "passive"))
      (node (ref "U5") (pin "6") (pinfunction "1Y_6") (pintype "output"))
    )
    (net (code "93") (name "Net-(Q2-D)") (class "Default")
      (node (ref "Q2") (pin "3") (pinfunction "D_3") (pintype "passive"))
      (node (ref "R16") (pin "2") (pinfunction "2_2") (pintype "passive"))
      (node (ref "U5") (pin "3") (pinfunction "2A_3") (pintype "input"))
    )
    (net (code "94") (name "Net-(Q10-D)") (class "Default")
      (node (ref "Q10") (pin "3") (pinfunction "D_3") (pintype "passive"))
      (node (ref "R129") (pin "2") (pinfunction "2_2") (pintype "passive"))
    )
    (net (code "95") (name "Net-(Q10-G)") (class "Default")
      (node (ref "Q10") (pin "1") (pinfunction "G_1") (pintype "passive"))
      (node (ref "U51") (pin "6") (pinfunction "1Y_6") (pintype "output"))
    )
    (net (code "96") (name "Net-(Q11-D)") (class "Default")
      (node (ref "Q11") (pin "3") (pinfunction "D_3") (pintype "passive"))
      (node (ref "R130") (pin "2") (pinfunction "2_2") (pintype "passive"))
    )
    (net (code "97") (name "Net-(Q11-G)") (class "Default")
      (node (ref "Q11") (pin "1") (pinfunction "G_1") (pintype "passive"))
      (node (ref "U51") (pin "4") (pinfunction "2Y_4") (pintype "output"))
    )
    (net (code "98") (name "Net-(Q12-D)") (class "Default")
      (node (ref "Q12") (pin "3") (pinfunction "D_3") (pintype "passive"))
      (node (ref "R131") (pin "2") (pinfunction "2_2") (pintype "passive"))
      (node (ref "U52") (pin "1") (pinfunction "1A_1") (pintype "input"))
    )
    (net (code "99") (name "Net-(Q13-D)") (class "Default")
      (node (ref "Q13") (pin "3") (pinfunction "D_3") (pintype "passive"))
      (node (ref "R132") (pin "2") (pinfunction "2_2") (pintype "passive"))
      (node (ref "U52") (pin "3") (pinfunction "2A_3") (pintype "input"))
    )
    (net (code "100") (name "unconnected-(J3A-(S)ATA_ACT#-PadA28)") (class "Default")
      (node (ref "J3") (pin "A28") (pinfunction "(S)ATA_ACT#_A28") (pintype "passive"))
    )
    (net (code "101") (name "unconnected-(J3A-AC{slash}HDA_BITCLK-PadA32)") (class "Default")
      (node (ref "J3") (pin "A32") (pinfunction "AC/HDA_BITCLK_A32") (pintype "passive"))
    )
    (net (code "102") (name "unconnected-(J3A-AC{slash}HDA_RST#-PadA30)") (class "Default")
      (node (ref "J3") (pin "A30") (pinfunction "AC/HDA_RST#_A30") (pintype "passive"))
    )
    (net (code "103") (name "unconnected-(J3A-AC{slash}HDA_SDOUT-PadA33)") (class "Default")
      (node (ref "J3") (pin "A33") (pinfunction "AC/HDA_SDOUT_A33") (pintype "passive"))
    )
    (net (code "104") (name "unconnected-(J3A-AC{slash}HDA_SYNC-PadA29)") (class "Default")
      (node (ref "J3") (pin "A29") (pinfunction "AC/HDA_SYNC_A29") (pintype "passive"))
    )
    (net (code "105") (name "unconnected-(J3A-BATLOW#-PadA27)") (class "Default")
      (node (ref "J3") (pin "A27") (pinfunction "BATLOW#_A27") (pintype "passive"))
    )
    (net (code "106") (name "unconnected-(J3A-BIOS_DIS0#-PadA34)") (class "Default")
      (node (ref "J3") (pin "A34") (pinfunction "BIOS_DIS0#_A34") (pintype "passive"))
    )
    (net (code "107") (name "unconnected-(J3A-GPI1-PadA63)") (class "Default")
      (node (ref "J3") (pin "A63") (pinfunction "GPI1_A63") (pintype "passive"))
    )
    (net (code "108") (name "unconnected-(J3A-GPI2-PadA67)") (class "Default")
      (node (ref "J3") (pin "A67") (pinfunction "GPI2_A67") (pintype "passive"))
    )
    (net (code "109") (name "unconnected-(J3A-GPI3-PadA85)") (class "Default")
      (node (ref "J3") (pin "A85") (pinfunction "GPI3_A85") (pintype "passive"))
    )
    (net (code "110") (name "unconnected-(J3A-GPIO-PadA54)") (class "Default")
      (node (ref "J3") (pin "A54") (pinfunction "GPIO_A54") (pintype "passive"))
    )
    (net (code "111") (name "unconnected-(J3A-GPO0-PadA93)") (class "Default")
      (node (ref "J3") (pin "A93") (pinfunction "GPO0_A93") (pintype "passive"))
    )
    (net (code "112") (name "unconnected-(J3A-LID#-PadA103)") (class "Default")
      (node (ref "J3") (pin "A103") (pinfunction "LID#_A103") (pintype "passive"))
    )
    (net (code "113") (name "unconnected-(J3A-LPC_SERIRQ-PadA50)") (class "Default")
      (node (ref "J3") (pin "A50") (pinfunction "LPC_SERIRQ_A50") (pintype "passive"))
    )
    (net (code "114") (name "unconnected-(J3A-LVDS_A0+-PadA71)") (class "Default")
      (node (ref "J3") (pin "A71") (pinfunction "LVDS_A0+_A71") (pintype "passive"))
    )
    (net (code "115") (name "unconnected-(J3A-LVDS_A0--PadA72)") (class "Default")
      (node (ref "J3") (pin "A72") (pinfunction "LVDS_A0-_A72") (pintype "passive"))
    )
    (net (code "116") (name "unconnected-(J3A-LVDS_A1+-PadA73)") (class "Default")
      (node (ref "J3") (pin "A73") (pinfunction "LVDS_A1+_A73") (pintype "passive"))
    )
    (net (code "117") (name "unconnected-(J3A-LVDS_A1--PadA74)") (class "Default")
      (node (ref "J3") (pin "A74") (pinfunction "LVDS_A1-_A74") (pintype "passive"))
    )
    (net (code "118") (name "unconnected-(J3A-LVDS_A2+-PadA75)") (class "Default")
      (node (ref "J3") (pin "A75") (pinfunction "LVDS_A2+_A75") (pintype "passive"))
    )
    (net (code "119") (name "unconnected-(J3A-LVDS_A2--PadA76)") (class "Default")
      (node (ref "J3") (pin "A76") (pinfunction "LVDS_A2-_A76") (pintype "passive"))
    )
    (net (code "120") (name "unconnected-(J3A-LVDS_A3+-PadA78)") (class "Default")
      (node (ref "J3") (pin "A78") (pinfunction "LVDS_A3+_A78") (pintype "passive"))
    )
    (net (code "121") (name "unconnected-(J3A-LVDS_A3--PadA79)") (class "Default")
      (node (ref "J3") (pin "A79") (pinfunction "LVDS_A3-_A79") (pintype "passive"))
    )
    (net (code "122") (name "unconnected-(J3A-LVDS_A_CK+-PadA81)") (class "Default")
      (node (ref "J3") (pin "A81") (pinfunction "LVDS_A_CK+_A81") (pintype "passive"))
    )
    (net (code "123") (name "unconnected-(J3A-LVDS_A_CK--PadA82)") (class "Default")
      (node (ref "J3") (pin "A82") (pinfunction "LVDS_A_CK-_A82") (pintype "passive"))
    )
    (net (code "124") (name "unconnected-(J3A-LVDS_I2C_CK-PadA83)") (class "Default")
      (node (ref "J3") (pin "A83") (pinfunction "LVDS_I2C_CK_A83") (pintype "passive"))
    )
    (net (code "125") (name "unconnected-(J3A-LVDS_I2C_DAT-PadA84)") (class "Default")
      (node (ref "J3") (pin "A84") (pinfunction "LVDS_I2C_DAT_A84") (pintype "passive"))
    )
    (net (code "126") (name "unconnected-(J3A-LVDS_VDD_EN-PadA77)") (class "Default")
      (node (ref "J3") (pin "A77") (pinfunction "LVDS_VDD_EN_A77") (pintype "passive"))
    )
    (net (code "127") (name "unconnected-(J3A-PCIE_TX1+-PadA64)") (class "Default")
      (node (ref "J3") (pin "A64") (pinfunction "PCIE_TX1+_A64") (pintype "passive"))
    )
    (net (code "128") (name "unconnected-(J3A-PCIE_TX1--PadA65)") (class "Default")
      (node (ref "J3") (pin "A65") (pinfunction "PCIE_TX1-_A65") (pintype "passive"))
    )
    (net (code "129") (name "unconnected-(J3A-PCIE_TX2+-PadA61)") (class "Default")
      (node (ref "J3") (pin "A61") (pinfunction "PCIE_TX2+_A61") (pintype "passive"))
    )
    (net (code "130") (name "unconnected-(J3A-PCIE_TX2--PadA62)") (class "Default")
      (node (ref "J3") (pin "A62") (pinfunction "PCIE_TX2-_A62") (pintype "passive"))
    )
    (net (code "131") (name "unconnected-(J3A-PCIE_TX3+-PadA58)") (class "Default")
      (node (ref "J3") (pin "A58") (pinfunction "PCIE_TX3+_A58") (pintype "passive"))
    )
    (net (code "132") (name "unconnected-(J3A-PCIE_TX3--PadA59)") (class "Default")
      (node (ref "J3") (pin "A59") (pinfunction "PCIE_TX3-_A59") (pintype "passive"))
    )
    (net (code "133") (name "unconnected-(J3A-RSVD-PadA52)") (class "Default")
      (node (ref "J3") (pin "A52") (pinfunction "RSVD_A52") (pintype "passive"))
    )
    (net (code "134") (name "unconnected-(J3A-RSVD-PadA53)") (class "Default")
      (node (ref "J3") (pin "A53") (pinfunction "RSVD_A53") (pintype "passive"))
    )
    (net (code "135") (name "unconnected-(J3A-RSVD-PadA55)") (class "Default")
      (node (ref "J3") (pin "A55") (pinfunction "RSVD_A55") (pintype "passive"))
    )
    (net (code "136") (name "unconnected-(J3A-RSVD-PadA56)") (class "Default")
      (node (ref "J3") (pin "A56") (pinfunction "RSVD_A56") (pintype "passive"))
    )
    (net (code "137") (name "unconnected-(J3A-RSVD-PadA86)") (class "Default")
      (node (ref "J3") (pin "A86") (pinfunction "RSVD_A86") (pintype "passive"))
    )
    (net (code "138") (name "unconnected-(J3A-SATA0_RX+-PadA19)") (class "Default")
      (node (ref "J3") (pin "A19") (pinfunction "SATA0_RX+_A19") (pintype "passive"))
    )
    (net (code "139") (name "unconnected-(J3A-SATA0_RX--PadA20)") (class "Default")
      (node (ref "J3") (pin "A20") (pinfunction "SATA0_RX-_A20") (pintype "passive"))
    )
    (net (code "140") (name "unconnected-(J3A-SATA0_TX+-PadA16)") (class "Default")
      (node (ref "J3") (pin "A16") (pinfunction "SATA0_TX+_A16") (pintype "passive"))
    )
    (net (code "141") (name "unconnected-(J3A-SATA0_TX--PadA17)") (class "Default")
      (node (ref "J3") (pin "A17") (pinfunction "SATA0_TX-_A17") (pintype "passive"))
    )
    (net (code "142") (name "unconnected-(J3A-SPI_CLK-PadA94)") (class "Default")
      (node (ref "J3") (pin "A94") (pinfunction "SPI_CLK_A94") (pintype "passive"))
    )
    (net (code "143") (name "unconnected-(J3A-SPI_MISO-PadA92)") (class "Default")
      (node (ref "J3") (pin "A92") (pinfunction "SPI_MISO_A92") (pintype "passive"))
    )
    (net (code "144") (name "unconnected-(J3A-SPI_MOSI-PadA95)") (class "Default")
      (node (ref "J3") (pin "A95") (pinfunction "SPI_MOSI_A95") (pintype "passive"))
    )
    (net (code "145") (name "unconnected-(J3A-SPI_POWER-PadA91)") (class "Default")
      (node (ref "J3") (pin "A91") (pinfunction "SPI_POWER_A91") (pintype "passive"))
    )
    (net (code "146") (name "unconnected-(J3A-SUS_S3#-PadA15)") (class "Default")
      (node (ref "J3") (pin "A15") (pinfunction "SUS_S3#_A15") (pintype "passive"))
    )
    (net (code "147") (name "unconnected-(J3A-SUS_S4#-PadA18)") (class "Default")
      (node (ref "J3") (pin "A18") (pinfunction "SUS_S4#_A18") (pintype "passive"))
    )
    (net (code "148") (name "unconnected-(J3A-SUS_S5#-PadA24)") (class "Default")
      (node (ref "J3") (pin "A24") (pinfunction "SUS_S5#_A24") (pintype "passive"))
    )
    (net (code "149") (name "unconnected-(J3A-THRMTRIP#-PadA35)") (class "Default")
      (node (ref "J3") (pin "A35") (pinfunction "THRMTRIP#_A35") (pintype "passive"))
    )
    (net (code "150") (name "unconnected-(J3A-TPM_PP-PadA96)") (class "Default")
      (node (ref "J3") (pin "A96") (pinfunction "TPM_PP_A96") (pintype "passive"))
    )
    (net (code "151") (name "unconnected-(J3A-TYPE10#-PadA97)") (class "Default")
      (node (ref "J3") (pin "A97") (pinfunction "TYPE10#_A97") (pintype "passive"))
    )
    (net (code "152") (name "unconnected-(J3A-USB_6_7_OC#-PadA38)") (class "Default")
      (node (ref "J3") (pin "A38") (pinfunction "USB_6_7_OC#_A38") (pintype "passive"))
    )
    (net (code "153") (name "unconnected-(J3A-eDP_HPD-PadA87)") (class "Default")
      (node (ref "J3") (pin "A87") (pinfunction "eDP_HPD_A87") (pintype "passive"))
    )
    (net (code "154") (name "unconnected-(J3B-AC{slash}HDA_SDIN0-PadB30)") (class "Default")
      (node (ref "J3") (pin "B30") (pinfunction "AC/HDA_SDIN0_B30") (pintype "passive"))
    )
    (net (code "155") (name "unconnected-(J3B-AC{slash}HDA_SDIN1-PadB29)") (class "Default")
      (node (ref "J3") (pin "B29") (pinfunction "AC/HDA_SDIN1_B29") (pintype "passive"))
    )
    (net (code "156") (name "unconnected-(J3B-AC{slash}HDA_SDIN2-PadB28)") (class "Default")
      (node (ref "J3") (pin "B28") (pinfunction "AC/HDA_SDIN2_B28") (pintype "passive"))
    )
    (net (code "157") (name "unconnected-(J3B-BIOS_DIS1#-PadB88)") (class "Default")
      (node (ref "J3") (pin "B88") (pinfunction "BIOS_DIS1#_B88") (pintype "passive"))
    )
    (net (code "158") (name "unconnected-(J3B-DDI0_PAIR4+-PadB77)") (class "Default")
      (node (ref "J3") (pin "B77") (pinfunction "DDI0_PAIR4+_B77") (pintype "passive"))
    )
    (net (code "159") (name "unconnected-(J3B-DDI0_PAIR4--PadB78)") (class "Default")
      (node (ref "J3") (pin "B78") (pinfunction "DDI0_PAIR4-_B78") (pintype "passive"))
    )
    (net (code "160") (name "unconnected-(J3B-DDI0_PAIR5+-PadB91)") (class "Default")
      (node (ref "J3") (pin "B91") (pinfunction "DDI0_PAIR5+_B91") (pintype "passive"))
    )
    (net (code "161") (name "unconnected-(J3B-DDI0_PAIR5--PadB92)") (class "Default")
      (node (ref "J3") (pin "B92") (pinfunction "DDI0_PAIR5-_B92") (pintype "passive"))
    )
    (net (code "162") (name "unconnected-(J3B-DDI0_PAIR6+-PadB93)") (class "Default")
      (node (ref "J3") (pin "B93") (pinfunction "DDI0_PAIR6+_B93") (pintype "passive"))
    )
    (net (code "163") (name "unconnected-(J3B-DDI0_PAIR6--PadB94)") (class "Default")
      (node (ref "J3") (pin "B94") (pinfunction "DDI0_PAIR6-_B94") (pintype "passive"))
    )
    (net (code "164") (name "unconnected-(J3B-EXCD1_CPPE#-PadB48)") (class "Default")
      (node (ref "J3") (pin "B48") (pinfunction "EXCD1_CPPE#_B48") (pintype "passive"))
    )
    (net (code "165") (name "unconnected-(J3B-EXCD1_PERST#-PadB47)") (class "Default")
      (node (ref "J3") (pin "B47") (pinfunction "EXCD1_PERST#_B47") (pintype "passive"))
    )
    (net (code "166") (name "unconnected-(J3B-GPO1-PadB54)") (class "Default")
      (node (ref "J3") (pin "B54") (pinfunction "GPO1_B54") (pintype "passive"))
    )
    (net (code "167") (name "unconnected-(J3B-GPO2-PadB57)") (class "Default")
      (node (ref "J3") (pin "B57") (pinfunction "GPO2_B57") (pintype "passive"))
    )
    (net (code "168") (name "unconnected-(J3B-GPO3-PadB63)") (class "Default")
      (node (ref "J3") (pin "B63") (pinfunction "GPO3_B63") (pintype "passive"))
    )
    (net (code "169") (name "unconnected-(J3B-I2C_CK-PadB33)") (class "Default")
      (node (ref "J3") (pin "B33") (pinfunction "I2C_CK_B33") (pintype "passive"))
    )
    (net (code "170") (name "unconnected-(J3B-I2C_DAT-PadB34)") (class "Default")
      (node (ref "J3") (pin "B34") (pinfunction "I2C_DAT_B34") (pintype "passive"))
    )
    (net (code "171") (name "unconnected-(J3B-LPC_AD0-PadB4)") (class "Default")
      (node (ref "J3") (pin "B4") (pinfunction "LPC_AD0_B4") (pintype "passive"))
    )
    (net (code "172") (name "unconnected-(J3B-LPC_AD1-PadB5)") (class "Default")
      (node (ref "J3") (pin "B5") (pinfunction "LPC_AD1_B5") (pintype "passive"))
    )
    (net (code "173") (name "unconnected-(J3B-LPC_AD2-PadB6)") (class "Default")
      (node (ref "J3") (pin "B6") (pinfunction "LPC_AD2_B6") (pintype "passive"))
    )
    (net (code "174") (name "unconnected-(J3B-LPC_AD3-PadB7)") (class "Default")
      (node (ref "J3") (pin "B7") (pinfunction "LPC_AD3_B7") (pintype "passive"))
    )
    (net (code "175") (name "unconnected-(J3B-LPC_CLK-PadB10)") (class "Default")
      (node (ref "J3") (pin "B10") (pinfunction "LPC_CLK_B10") (pintype "passive"))
    )
    (net (code "176") (name "unconnected-(J3B-LPC_DRQ0#-PadB8)") (class "Default")
      (node (ref "J3") (pin "B8") (pinfunction "LPC_DRQ0#_B8") (pintype "passive"))
    )
    (net (code "177") (name "unconnected-(J3B-LPC_DRQ1#-PadB9)") (class "Default")
      (node (ref "J3") (pin "B9") (pinfunction "LPC_DRQ1#_B9") (pintype "passive"))
    )
    (net (code "178") (name "unconnected-(J3B-LPC_FRAME#-PadB3)") (class "Default")
      (node (ref "J3") (pin "B3") (pinfunction "LPC_FRAME#_B3") (pintype "passive"))
    )
    (net (code "179") (name "unconnected-(J3B-LVDC_BKLT_CTRL-PadB83)") (class "Default")
      (node (ref "J3") (pin "B83") (pinfunction "LVDC_BKLT_CTRL_B83") (pintype "passive"))
    )
    (net (code "180") (name "unconnected-(J3B-LVDC_BKLT_EN-PadB79)") (class "Default")
      (node (ref "J3") (pin "B79") (pinfunction "LVDC_BKLT_EN_B79") (pintype "passive"))
    )
    (net (code "181") (name "unconnected-(J3B-PCIE_RX1+-PadB64)") (class "Default")
      (node (ref "J3") (pin "B64") (pinfunction "PCIE_RX1+_B64") (pintype "passive"))
    )
    (net (code "182") (name "unconnected-(J3B-PCIE_RX1--PadB65)") (class "Default")
      (node (ref "J3") (pin "B65") (pinfunction "PCIE_RX1-_B65") (pintype "passive"))
    )
    (net (code "183") (name "unconnected-(J3B-PCIE_RX2+-PadB61)") (class "Default")
      (node (ref "J3") (pin "B61") (pinfunction "PCIE_RX2+_B61") (pintype "passive"))
    )
    (net (code "184") (name "unconnected-(J3B-PCIE_RX2--PadB62)") (class "Default")
      (node (ref "J3") (pin "B62") (pinfunction "PCIE_RX2-_B62") (pintype "passive"))
    )
    (net (code "185") (name "unconnected-(J3B-PCIE_RX3+-PadB58)") (class "Default")
      (node (ref "J3") (pin "B58") (pinfunction "PCIE_RX3+_B58") (pintype "passive"))
    )
    (net (code "186") (name "unconnected-(J3B-PCIE_RX3--PadB59)") (class "Default")
      (node (ref "J3") (pin "B59") (pinfunction "PCIE_RX3-_B59") (pintype "passive"))
    )
    (net (code "187") (name "unconnected-(J3B-PWR_OK-PadB24)") (class "Default")
      (node (ref "J3") (pin "B24") (pinfunction "PWR_OK_B24") (pintype "passive"))
    )
    (net (code "188") (name "unconnected-(J3B-RSVD-PadB52)") (class "Default")
      (node (ref "J3") (pin "B52") (pinfunction "RSVD_B52") (pintype "passive"))
    )
    (net (code "189") (name "unconnected-(J3B-RSVD-PadB53)") (class "Default")
      (node (ref "J3") (pin "B53") (pinfunction "RSVD_B53") (pintype "passive"))
    )
    (net (code "190") (name "unconnected-(J3B-RSVD-PadB55)") (class "Default")
      (node (ref "J3") (pin "B55") (pinfunction "RSVD_B55") (pintype "passive"))
    )
    (net (code "191") (name "unconnected-(J3B-RSVD-PadB56)") (class "Default")
      (node (ref "J3") (pin "B56") (pinfunction "RSVD_B56") (pintype "passive"))
    )
    (net (code "192") (name "unconnected-(J3B-SATA1_RX+-PadB19)") (class "Default")
      (node (ref "J3") (pin "B19") (pinfunction "SATA1_RX+_B19") (pintype "passive"))
    )
    (net (code "193") (name "unconnected-(J3B-SATA1_RX--PadB20)") (class "Default")
      (node (ref "J3") (pin "B20") (pinfunction "SATA1_RX-_B20") (pintype "passive"))
    )
    (net (code "194") (name "unconnected-(J3B-SATA1_TX+-PadB16)") (class "Default")
      (node (ref "J3") (pin "B16") (pinfunction "SATA1_TX+_B16") (pintype "passive"))
    )
    (net (code "195") (name "unconnected-(J3B-SATA1_TX--PadB17)") (class "Default")
      (node (ref "J3") (pin "B17") (pinfunction "SATA1_TX-_B17") (pintype "passive"))
    )
    (net (code "196") (name "unconnected-(J3B-SLEEP#-PadB103)") (class "Default")
      (node (ref "J3") (pin "B103") (pinfunction "SLEEP#_B103") (pintype "passive"))
    )
    (net (code "197") (name "unconnected-(J3B-SPI_CS#-PadB97)") (class "Default")
      (node (ref "J3") (pin "B97") (pinfunction "SPI_CS#_B97") (pintype "passive"))
    )
    (net (code "198") (name "unconnected-(J3B-SPKR-PadB32)") (class "Default")
      (node (ref "J3") (pin "B32") (pinfunction "SPKR_B32") (pintype "passive"))
    )
    (net (code "199") (name "unconnected-(J3B-SUS_STAT#-PadB18)") (class "Default")
      (node (ref "J3") (pin "B18") (pinfunction "SUS_STAT#_B18") (pintype "passive"))
    )
    (net (code "200") (name "unconnected-(J3B-THRM#-PadB35)") (class "Default")
      (node (ref "J3") (pin "B35") (pinfunction "THRM#_B35") (pintype "passive"))
    )
    (net (code "201") (name "unconnected-(J3B-USB_HOST_PRSNT-PadB96)") (class "Default")
      (node (ref "J3") (pin "B96") (pinfunction "USB_HOST_PRSNT_B96") (pintype "passive"))
    )
    (net (code "202") (name "unconnected-(J3B-WAKE1#-PadB67)") (class "Default")
      (node (ref "J3") (pin "B67") (pinfunction "WAKE1#_B67") (pintype "passive"))
    )
    (net (code "203") (name "unconnected-(J3B-WDT-PadB27)") (class "Default")
      (node (ref "J3") (pin "B27") (pinfunction "WDT_B27") (pintype "passive"))
    )
  )
)
